# lamp_sch.net
KiCad netlist of a schematic drawn in EAGLE
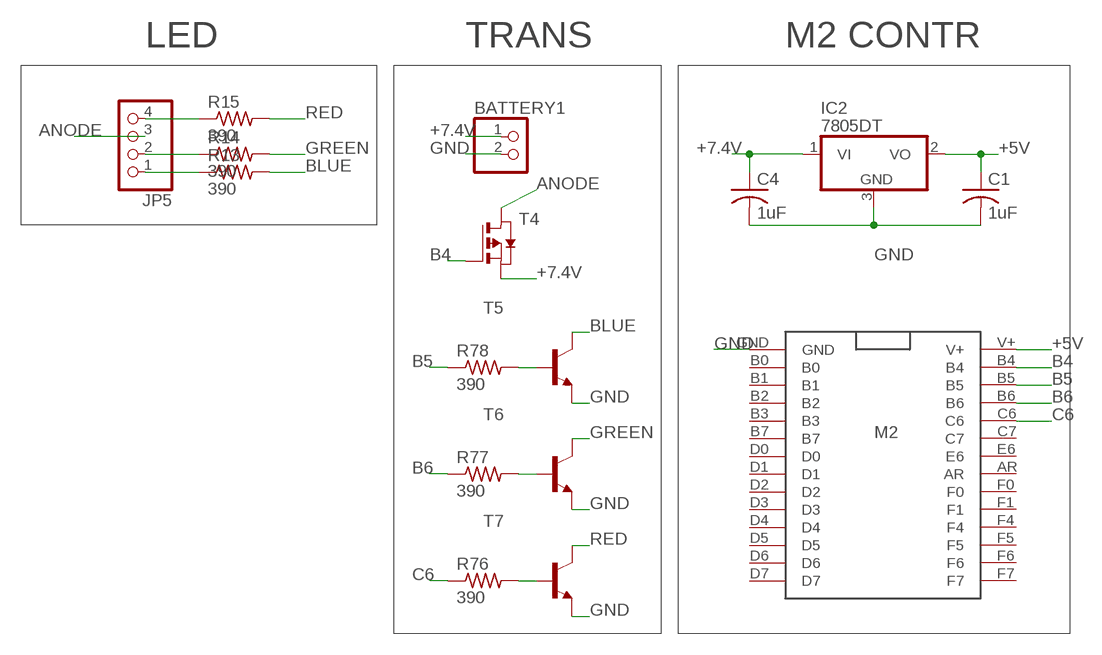
[diagram p0: schematic, sheet 1]

(export (version "E")
  (design (tool "Eeschema 10.0.6"))
  (components
    (comp (ref "BATTERY1")
      (value "PINHD-1X2")
      (footprint "eagle-import:1X02")
      (libsource (lib "eagle-import") (part "PINHD-1X2"))
    )
    (comp (ref "C1")
      (value "1uF")
      (footprint "eagle-import:C0603")
      (libsource (lib "eagle-import") (part "C-USC0603"))
    )
    (comp (ref "C4")
      (value "1uF")
      (footprint "eagle-import:C0603")
      (libsource (lib "eagle-import") (part "C-USC0603"))
    )
    (comp (ref "IC2")
      (value "7805DT")
      (footprint "eagle-import:TO252")
      (libsource (lib "eagle-import") (part "78DT05"))
    )
    (comp (ref "JP5")
      (value "PINHD-1X4")
      (footprint "eagle-import:1X04")
      (libsource (lib "eagle-import") (part "PINHD-1X4"))
    )
    (comp (ref "R13")
      (value "390")
      (footprint "eagle-import:R0603")
      (libsource (lib "eagle-import") (part "R-US_R0603"))
    )
    (comp (ref "R14")
      (value "390")
      (footprint "eagle-import:R0603")
      (libsource (lib "eagle-import") (part "R-US_R0603"))
    )
    (comp (ref "R15")
      (value "390")
      (footprint "eagle-import:R0603")
      (libsource (lib "eagle-import") (part "R-US_R0603"))
    )
    (comp (ref "R76")
      (value "390")
      (footprint "eagle-import:R0603")
      (libsource (lib "eagle-import") (part "R-US_R0603"))
    )
    (comp (ref "R77")
      (value "390")
      (footprint "eagle-import:R0603")
      (libsource (lib "eagle-import") (part "R-US_R0603"))
    )
    (comp (ref "R78")
      (value "390")
      (footprint "eagle-import:R0603")
      (libsource (lib "eagle-import") (part "R-US_R0603"))
    )
    (comp (ref "T4")
      (value "PMOSSOT23")
      (footprint "eagle-import:SOT-23")
      (libsource (lib "eagle-import") (part "PMOSSOT23"))
    )
    (comp (ref "T5")
      (value "MMBT3904LT1-NPN-SOT23-BEC")
      (footprint "eagle-import:SOT23-BEC")
      (libsource (lib "eagle-import") (part "-NPN-SOT23-BECMMBT3904LT1"))
    )
    (comp (ref "T6")
      (value "MMBT3904LT1-NPN-SOT23-BEC")
      (footprint "eagle-import:SOT23-BEC")
      (libsource (lib "eagle-import") (part "-NPN-SOT23-BECMMBT3904LT1"))
    )
    (comp (ref "T7")
      (value "MMBT3904LT1-NPN-SOT23-BEC")
      (footprint "eagle-import:SOT23-BEC")
      (libsource (lib "eagle-import") (part "-NPN-SOT23-BECMMBT3904LT1"))
    )
    (comp (ref "U$2") (value "M2") (footprint "eagle-import:M2") (libsource (lib "eagle-import") (part "M2")))
  )
  (nets
    (net (code "1") (name "/+5V") (class "Default")
      (node (ref "C1") (pin "1") (pinfunction "1_1") (pintype "passive"))
      (node (ref "IC2") (pin "2") (pinfunction "VO_2") (pintype "passive"))
      (node (ref "U$2") (pin "V+") (pinfunction "V+_V+") (pintype "bidirectional"))
    )
    (net (code "2") (name "/+7.4V") (class "Default")
      (node (ref "BATTERY1") (pin "1") (pinfunction "1_1") (pintype "passive"))
      (node (ref "C4") (pin "1") (pinfunction "1_1") (pintype "passive"))
      (node (ref "IC2") (pin "1") (pinfunction "VI_1") (pintype "input"))
      (node (ref "T4") (pin "2") (pinfunction "S_2") (pintype "passive"))
    )
    (net (code "3") (name "/ANODE") (class "Default")
      (node (ref "JP5") (pin "3") (pinfunction "3_3") (pintype "passive"))
      (node (ref "T4") (pin "1") (pinfunction "D_1") (pintype "passive"))
    )
    (net (code "4") (name "/B4") (class "Default")
      (node (ref "T4") (pin "3") (pinfunction "G_3") (pintype "passive"))
      (node (ref "U$2") (pin "B4") (pinfunction "B4_B4") (pintype "bidirectional"))
    )
    (net (code "5") (name "/B5") (class "Default")
      (node (ref "R78") (pin "1") (pinfunction "1_1") (pintype "passive"))
      (node (ref "U$2") (pin "B5") (pinfunction "B5_B5") (pintype "bidirectional"))
    )
    (net (code "6") (name "/B6") (class "Default")
      (node (ref "R77") (pin "1") (pinfunction "1_1") (pintype "passive"))
      (node (ref "U$2") (pin "B6") (pinfunction "B6_B6") (pintype "bidirectional"))
    )
    (net (code "7") (name "/BLUE") (class "Default")
      (node (ref "R13") (pin "2") (pinfunction "2_2") (pintype "passive"))
      (node (ref "T5") (pin "C") (pinfunction "C_C") (pintype "passive"))
    )
    (net (code "8") (name "/C6") (class "Default")
      (node (ref "R76") (pin "1") (pinfunction "1_1") (pintype "passive"))
      (node (ref "U$2") (pin "C6") (pinfunction "C6_C6") (pintype "bidirectional"))
    )
    (net (code "9") (name "/GND") (class "Default")
      (node (ref "BATTERY1") (pin "2") (pinfunction "2_2") (pintype "passive"))
      (node (ref "C1") (pin "2") (pinfunction "2_2") (pintype "passive"))
      (node (ref "C4") (pin "2") (pinfunction "2_2") (pintype "passive"))
      (node (ref "IC2") (pin "3") (pinfunction "GND_3") (pintype "passive"))
      (node (ref "T5") (pin "E") (pinfunction "E_E") (pintype "passive"))
      (node (ref "T6") (pin "E") (pinfunction "E_E") (pintype "passive"))
      (node (ref "T7") (pin "E") (pinfunction "E_E") (pintype "passive"))
      (node (ref "U$2") (pin "GND") (pinfunction "GND_GND") (pintype "bidirectional"))
    )
    (net (code "10") (name "/GREEN") (class "Default")
      (node (ref "R14") (pin "2") (pinfunction "2_2") (pintype "passive"))
      (node (ref "T6") (pin "C") (pinfunction "C_C") (pintype "passive"))
    )
    (net (code "11") (name "/RED") (class "Default")
      (node (ref "R15") (pin "2") (pinfunction "2_2") (pintype "passive"))
      (node (ref "T7") (pin "C") (pinfunction "C_C") (pintype "passive"))
    )
    (net (code "12") (name "Net-(JP5-Pad1)") (class "Default")
      (node (ref "JP5") (pin "1") (pinfunction "1_1") (pintype "passive"))
      (node (ref "R13") (pin "1") (pinfunction "1_1") (pintype "passive"))
    )
    (net (code "13") (name "Net-(JP5-Pad2)") (class "Default")
      (node (ref "JP5") (pin "2") (pinfunction "2_2") (pintype "passive"))
      (node (ref "R14") (pin "1") (pinfunction "1_1") (pintype "passive"))
    )
    (net (code "14") (name "Net-(JP5-Pad4)") (class "Default")
      (node (ref "JP5") (pin "4") (pinfunction "4_4") (pintype "passive"))
      (node (ref "R15") (pin "1") (pinfunction "1_1") (pintype "passive"))
    )
    (net (code "15") (name "Net-(R76-Pad2)") (class "Default")
      (node (ref "R76") (pin "2") (pinfunction "2_2") (pintype "passive"))
      (node (ref "T7") (pin "B") (pinfunction "B_B") (pintype "passive"))
    )
    (net (code "16") (name "Net-(R77-Pad2)") (class "Default")
      (node (ref "R77") (pin "2") (pinfunction "2_2") (pintype "passive"))
      (node (ref "T6") (pin "B") (pinfunction "B_B") (pintype "passive"))
    )
    (net (code "17") (name "Net-(R78-Pad2)") (class "Default")
      (node (ref "R78") (pin "2") (pinfunction "2_2") (pintype "passive"))
      (node (ref "T5") (pin "B") (pinfunction "B_B") (pintype "passive"))
    )
    (net (code "18") (name "unconnected-(U$2-PadAR)") (class "Default")
      (node (ref "U$2") (pin "AR") (pinfunction "AR_AR") (pintype "bidirectional"))
    )
    (net (code "19") (name "unconnected-(U$2-PadB0)") (class "Default")
      (node (ref "U$2") (pin "B0") (pinfunction "B0_B0") (pintype "bidirectional"))
    )
    (net (code "20") (name "unconnected-(U$2-PadB1)") (class "Default")
      (node (ref "U$2") (pin "B1") (pinfunction "B1_B1") (pintype "bidirectional"))
    )
    (net (code "21") (name "unconnected-(U$2-PadB2)") (class "Default")
      (node (ref "U$2") (pin "B2") (pinfunction "B2_B2") (pintype "bidirectional"))
    )
    (net (code "22") (name "unconnected-(U$2-PadB3)") (class "Default")
      (node (ref "U$2") (pin "B3") (pinfunction "B3_B3") (pintype "bidirectional"))
    )
    (net (code "23") (name "unconnected-(U$2-PadB7)") (class "Default")
      (node (ref "U$2") (pin "B7") (pinfunction "B7_B7") (pintype "bidirectional"))
    )
    (net (code "24") (name "unconnected-(U$2-PadC7)") (class "Default")
      (node (ref "U$2") (pin "C7") (pinfunction "C7_C7") (pintype "bidirectional"))
    )
    (net (code "25") (name "unconnected-(U$2-PadD0)") (class "Default")
      (node (ref "U$2") (pin "D0") (pinfunction "D0_D0") (pintype "bidirectional"))
    )
    (net (code "26") (name "unconnected-(U$2-PadD1)") (class "Default")
      (node (ref "U$2") (pin "D1") (pinfunction "D1_D1") (pintype "bidirectional"))
    )
    (net (code "27") (name "unconnected-(U$2-PadD2)") (class "Default")
      (node (ref "U$2") (pin "D2") (pinfunction "D2_D2") (pintype "bidirectional"))
    )
    (net (code "28") (name "unconnected-(U$2-PadD3)") (class "Default")
      (node (ref "U$2") (pin "D3") (pinfunction "D3_D3") (pintype "bidirectional"))
    )
    (net (code "29") (name "unconnected-(U$2-PadD4)") (class "Default")
      (node (ref "U$2") (pin "D4") (pinfunction "D4_D4") (pintype "bidirectional"))
    )
    (net (code "30") (name "unconnected-(U$2-PadD5)") (class "Default")
      (node (ref "U$2") (pin "D5") (pinfunction "D5_D5") (pintype "bidirectional"))
    )
    (net (code "31") (name "unconnected-(U$2-PadD6)") (class "Default")
      (node (ref "U$2") (pin "D6") (pinfunction "D6_D6") (pintype "bidirectional"))
    )
    (net (code "32") (name "unconnected-(U$2-PadD7)") (class "Default")
      (node (ref "U$2") (pin "D7") (pinfunction "D7_D7") (pintype "bidirectional"))
    )
    (net (code "33") (name "unconnected-(U$2-PadE6)") (class "Default")
      (node (ref "U$2") (pin "E6") (pinfunction "E6_E6") (pintype "bidirectional"))
    )
    (net (code "34") (name "unconnected-(U$2-PadF0)") (class "Default")
      (node (ref "U$2") (pin "F0") (pinfunction "F0_F0") (pintype "bidirectional"))
    )
    (net (code "35") (name "unconnected-(U$2-PadF1)") (class "Default")
      (node (ref "U$2") (pin "F1") (pinfunction "F1_F1") (pintype "bidirectional"))
    )
    (net (code "36") (name "unconnected-(U$2-PadF4)") (class "Default")
      (node (ref "U$2") (pin "F4") (pinfunction "F4_F4") (pintype "bidirectional"))
    )
    (net (code "37") (name "unconnected-(U$2-PadF5)") (class "Default")
      (node (ref "U$2") (pin "F5") (pinfunction "F5_F5") (pintype "bidirectional"))
    )
    (net (code "38") (name "unconnected-(U$2-PadF6)") (class "Default")
      (node (ref "U$2") (pin "F6") (pinfunction "F6_F6") (pintype "bidirectional"))
    )
    (net (code "39") (name "unconnected-(U$2-PadF7)") (class "Default")
      (node (ref "U$2") (pin "F7") (pinfunction "F7_F7") (pintype "bidirectional"))
    )
  )
)
